# Receiver.net
KiCad netlist of a schematic drawn in Altium Designer
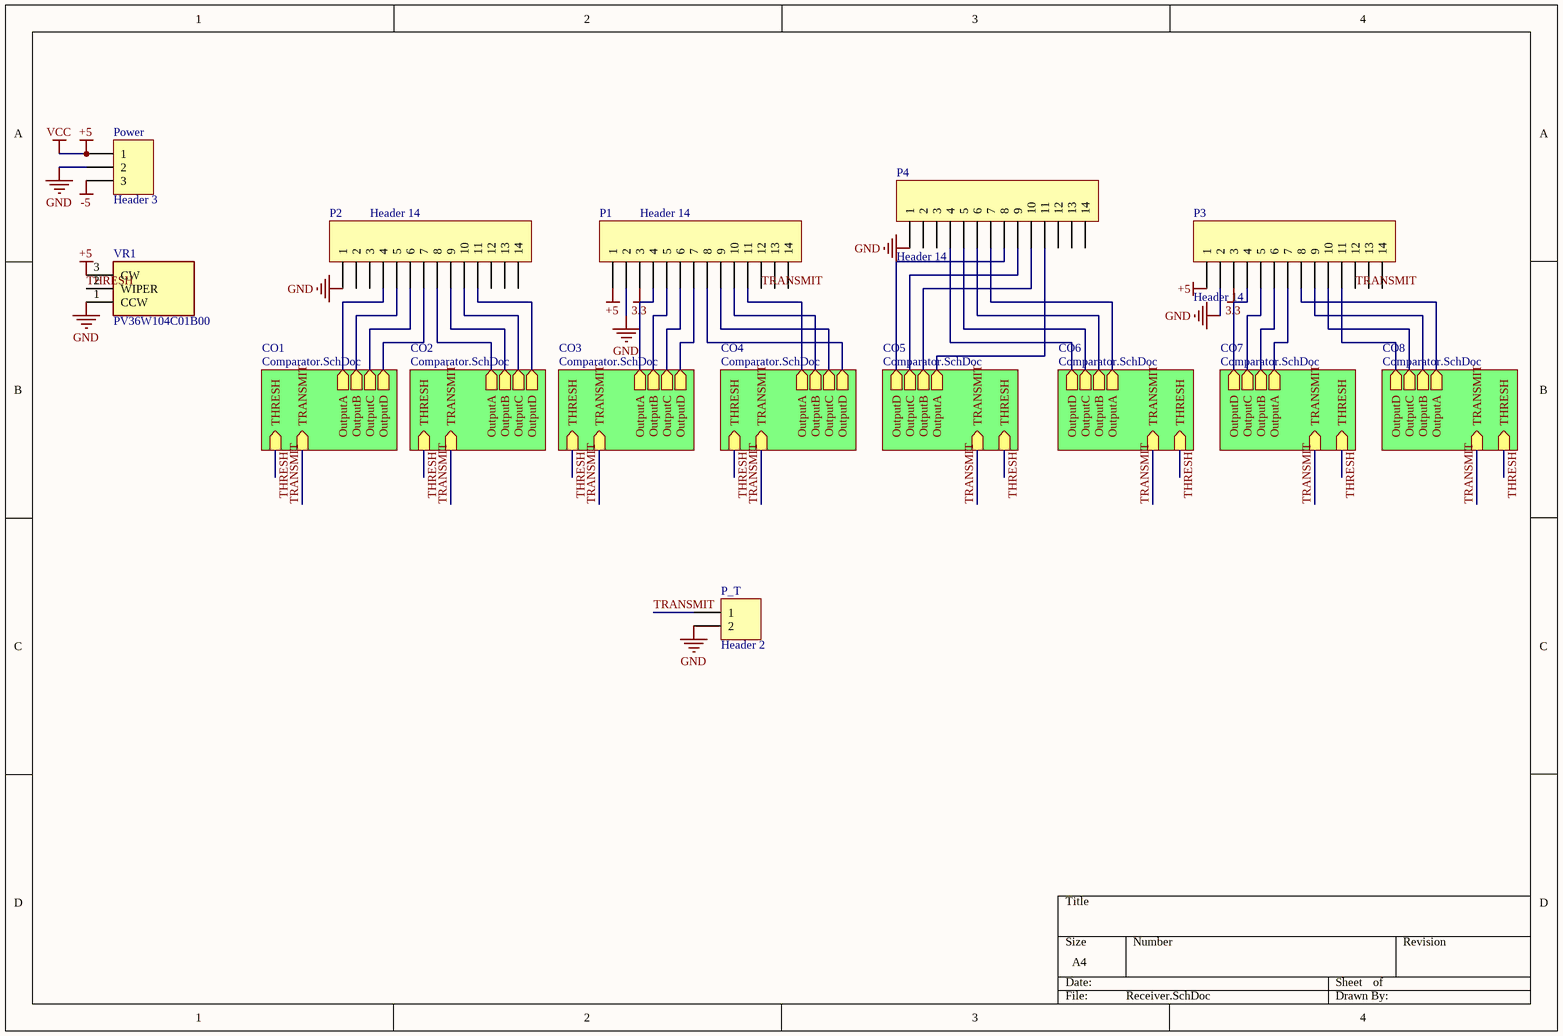
[diagram p0: Receiver.SchDoc]

(export (version "E")
  (design (tool "Eeschema 10.0.6"))
  (components
    (comp (ref "P1")
      (value "Header 14")
      (footprint "HDR1X14")
      (description "Header, 14-Pin")
      (fields (field (name "PUBLISHER") "Altium Limited"))
      (libsource (lib "Miscellaneous Connectors") (part "Header 14"))
    )
    (comp (ref "P2")
      (value "Header 14")
      (footprint "HDR1X14")
      (description "Header, 14-Pin")
      (fields (field (name "PUBLISHER") "Altium Limited"))
      (libsource (lib "Miscellaneous Connectors") (part "Header 14"))
    )
    (comp (ref "P3")
      (value "Header 14")
      (footprint "HDR1X14")
      (description "Header, 14-Pin")
      (fields (field (name "PUBLISHER") "Altium Limited"))
      (libsource (lib "Miscellaneous Connectors") (part "Header 14"))
    )
    (comp (ref "P4")
      (value "Header 14")
      (footprint "HDR1X14")
      (description "Header, 14-Pin")
      (fields (field (name "PUBLISHER") "Altium Limited"))
      (libsource (lib "Miscellaneous Connectors") (part "Header 14"))
    )
    (comp (ref "Power")
      (value "Header 3")
      (footprint "HDR1X3")
      (description "Header, 3-Pin")
      (fields (field (name "PUBLISHER") "Altium Limited"))
      (libsource (lib "Miscellaneous Connectors") (part "Header 3"))
    )
    (comp (ref "P_T")
      (value "Header 2")
      (footprint "HDR1X2")
      (description "Header, 2-Pin")
      (fields (field (name "PUBLISHER") "Altium Limited"))
      (libsource (lib "Miscellaneous Connectors") (part "Header 2"))
    )
    (comp (ref "VR1")
      (value "PV36W104C01B00")
      (footprint "SamacSys:PV36W")
      (description "Variable Resistor")
      (fields
        (field (name "MOUSER PART NUMBER") "81-PV36W104C01B00")
        (field (name "RS PART NUMBER") "7692160P")
      )
      (libsource (lib "*") (part "PV36W104C01B00"))
    )
  )
  (nets
    (net (code "1") (name "+5") (class "Default")
      (node (ref "P1") (pin "1") (pinfunction "1_1") (pintype "passive"))
      (node (ref "P3") (pin "1") (pinfunction "1_1") (pintype "passive"))
      (node (ref "Power") (pin "1") (pinfunction "1_1") (pintype "passive"))
      (node (ref "VR1") (pin "3") (pinfunction "CW_3") (pintype "passive"))
    )
    (net (code "2") (name "-5") (class "Default")
      (node (ref "Power") (pin "3") (pinfunction "3_3") (pintype "passive"))
    )
    (net (code "3") (name "/OutputA") (class "Default")
      (node (ref "P3") (pin "8") (pinfunction "8_8") (pintype "passive"))
    )
    (net (code "4") (name "/OutputA_1") (class "Default")
      (node (ref "P2") (pin "4") (pinfunction "4_4") (pintype "passive"))
    )
    (net (code "5") (name "/OutputA_2") (class "Default")
      (node (ref "P2") (pin "8") (pinfunction "8_8") (pintype "passive"))
    )
    (net (code "6") (name "/OutputA_3") (class "Default")
      (node (ref "P1") (pin "4") (pinfunction "4_4") (pintype "passive"))
    )
    (net (code "7") (name "/OutputA_4") (class "Default")
      (node (ref "P1") (pin "11") (pinfunction "11_11") (pintype "passive"))
    )
    (net (code "8") (name "/OutputA_5") (class "Default")
      (node (ref "P4") (pin "11") (pinfunction "11_11") (pintype "passive"))
    )
    (net (code "9") (name "/OutputA_6") (class "Default")
      (node (ref "P4") (pin "7") (pinfunction "7_7") (pintype "passive"))
    )
    (net (code "10") (name "/OutputA_7") (class "Default")
      (node (ref "P3") (pin "7") (pinfunction "7_7") (pintype "passive"))
    )
    (net (code "11") (name "/OutputB") (class "Default")
      (node (ref "P3") (pin "9") (pinfunction "9_9") (pintype "passive"))
    )
    (net (code "12") (name "/OutputB_1") (class "Default")
      (node (ref "P2") (pin "5") (pinfunction "5_5") (pintype "passive"))
    )
    (net (code "13") (name "/OutputB_2") (class "Default")
      (node (ref "P2") (pin "9") (pinfunction "9_9") (pintype "passive"))
    )
    (net (code "14") (name "/OutputB_3") (class "Default")
      (node (ref "P1") (pin "5") (pinfunction "5_5") (pintype "passive"))
    )
    (net (code "15") (name "/OutputB_4") (class "Default")
      (node (ref "P1") (pin "10") (pinfunction "10_10") (pintype "passive"))
    )
    (net (code "16") (name "/OutputB_5") (class "Default")
      (node (ref "P4") (pin "10") (pinfunction "10_10") (pintype "passive"))
    )
    (net (code "17") (name "/OutputB_6") (class "Default")
      (node (ref "P4") (pin "6") (pinfunction "6_6") (pintype "passive"))
    )
    (net (code "18") (name "/OutputB_7") (class "Default")
      (node (ref "P3") (pin "6") (pinfunction "6_6") (pintype "passive"))
    )
    (net (code "19") (name "/OutputC") (class "Default")
      (node (ref "P3") (pin "10") (pinfunction "10_10") (pintype "passive"))
    )
    (net (code "20") (name "/OutputC_1") (class "Default")
      (node (ref "P2") (pin "6") (pinfunction "6_6") (pintype "passive"))
    )
    (net (code "21") (name "/OutputC_2") (class "Default")
      (node (ref "P2") (pin "10") (pinfunction "10_10") (pintype "passive"))
    )
    (net (code "22") (name "/OutputC_3") (class "Default")
      (node (ref "P1") (pin "6") (pinfunction "6_6") (pintype "passive"))
    )
    (net (code "23") (name "/OutputC_4") (class "Default")
      (node (ref "P1") (pin "9") (pinfunction "9_9") (pintype "passive"))
    )
    (net (code "24") (name "/OutputC_5") (class "Default")
      (node (ref "P4") (pin "9") (pinfunction "9_9") (pintype "passive"))
    )
    (net (code "25") (name "/OutputC_6") (class "Default")
      (node (ref "P4") (pin "5") (pinfunction "5_5") (pintype "passive"))
    )
    (net (code "26") (name "/OutputC_7") (class "Default")
      (node (ref "P3") (pin "5") (pinfunction "5_5") (pintype "passive"))
    )
    (net (code "27") (name "/OutputD") (class "Default")
      (node (ref "P3") (pin "11") (pinfunction "11_11") (pintype "passive"))
    )
    (net (code "28") (name "/OutputD_1") (class "Default")
      (node (ref "P2") (pin "7") (pinfunction "7_7") (pintype "passive"))
    )
    (net (code "29") (name "/OutputD_2") (class "Default")
      (node (ref "P2") (pin "11") (pinfunction "11_11") (pintype "passive"))
    )
    (net (code "30") (name "/OutputD_3") (class "Default")
      (node (ref "P1") (pin "7") (pinfunction "7_7") (pintype "passive"))
    )
    (net (code "31") (name "/OutputD_4") (class "Default")
      (node (ref "P1") (pin "8") (pinfunction "8_8") (pintype "passive"))
    )
    (net (code "32") (name "/OutputD_5") (class "Default")
      (node (ref "P4") (pin "8") (pinfunction "8_8") (pintype "passive"))
    )
    (net (code "33") (name "/OutputD_6") (class "Default")
      (node (ref "P4") (pin "4") (pinfunction "4_4") (pintype "passive"))
    )
    (net (code "34") (name "/OutputD_7") (class "Default")
      (node (ref "P3") (pin "4") (pinfunction "4_4") (pintype "passive"))
    )
    (net (code "35") (name "/THRESH") (class "Default")
      (node (ref "VR1") (pin "2") (pinfunction "WIPER_2") (pintype "passive"))
    )
    (net (code "36") (name "/TRANSMIT") (class "Default")
      (node (ref "P1") (pin "12") (pinfunction "12_12") (pintype "passive"))
      (node (ref "P3") (pin "12") (pinfunction "12_12") (pintype "passive"))
      (node (ref "P_T") (pin "1") (pinfunction "1_1") (pintype "passive"))
    )
    (net (code "37") (name "3.3") (class "Default")
      (node (ref "P1") (pin "3") (pinfunction "3_3") (pintype "passive"))
      (node (ref "P3") (pin "3") (pinfunction "3_3") (pintype "passive"))
    )
    (net (code "38") (name "GND") (class "Default")
      (node (ref "P1") (pin "2") (pinfunction "2_2") (pintype "passive"))
      (node (ref "P2") (pin "1") (pinfunction "1_1") (pintype "passive"))
      (node (ref "P3") (pin "2") (pinfunction "2_2") (pintype "passive"))
      (node (ref "P4") (pin "1") (pinfunction "1_1") (pintype "passive"))
      (node (ref "P_T") (pin "2") (pinfunction "2_2") (pintype "passive"))
      (node (ref "Power") (pin "2") (pinfunction "2_2") (pintype "passive"))
      (node (ref "VR1") (pin "1") (pinfunction "CCW_1") (pintype "passive"))
    )
    (net (code "39") (name "unconnected-(P1-Pad13)") (class "Default")
      (node (ref "P1") (pin "13") (pinfunction "13_13") (pintype "passive"))
    )
    (net (code "40") (name "unconnected-(P1-Pad14)") (class "Default")
      (node (ref "P1") (pin "14") (pinfunction "14_14") (pintype "passive"))
    )
    (net (code "41") (name "unconnected-(P2-Pad2)") (class "Default")
      (node (ref "P2") (pin "2") (pinfunction "2_2") (pintype "passive"))
    )
    (net (code "42") (name "unconnected-(P2-Pad3)") (class "Default")
      (node (ref "P2") (pin "3") (pinfunction "3_3") (pintype "passive"))
    )
    (net (code "43") (name "unconnected-(P2-Pad12)") (class "Default")
      (node (ref "P2") (pin "12") (pinfunction "12_12") (pintype "passive"))
    )
    (net (code "44") (name "unconnected-(P2-Pad13)") (class "Default")
      (node (ref "P2") (pin "13") (pinfunction "13_13") (pintype "passive"))
    )
    (net (code "45") (name "unconnected-(P2-Pad14)") (class "Default")
      (node (ref "P2") (pin "14") (pinfunction "14_14") (pintype "passive"))
    )
    (net (code "46") (name "unconnected-(P3-Pad13)") (class "Default")
      (node (ref "P3") (pin "13") (pinfunction "13_13") (pintype "passive"))
    )
    (net (code "47") (name "unconnected-(P3-Pad14)") (class "Default")
      (node (ref "P3") (pin "14") (pinfunction "14_14") (pintype "passive"))
    )
    (net (code "48") (name "unconnected-(P4-Pad2)") (class "Default")
      (node (ref "P4") (pin "2") (pinfunction "2_2") (pintype "passive"))
    )
    (net (code "49") (name "unconnected-(P4-Pad3)") (class "Default")
      (node (ref "P4") (pin "3") (pinfunction "3_3") (pintype "passive"))
    )
    (net (code "50") (name "unconnected-(P4-Pad12)") (class "Default")
      (node (ref "P4") (pin "12") (pinfunction "12_12") (pintype "passive"))
    )
    (net (code "51") (name "unconnected-(P4-Pad13)") (class "Default")
      (node (ref "P4") (pin "13") (pinfunction "13_13") (pintype "passive"))
    )
    (net (code "52") (name "unconnected-(P4-Pad14)") (class "Default")
      (node (ref "P4") (pin "14") (pinfunction "14_14") (pintype "passive"))
    )
  )
)
